# connecter.net
KiCad netlist of a schematic drawn in Altium Designer
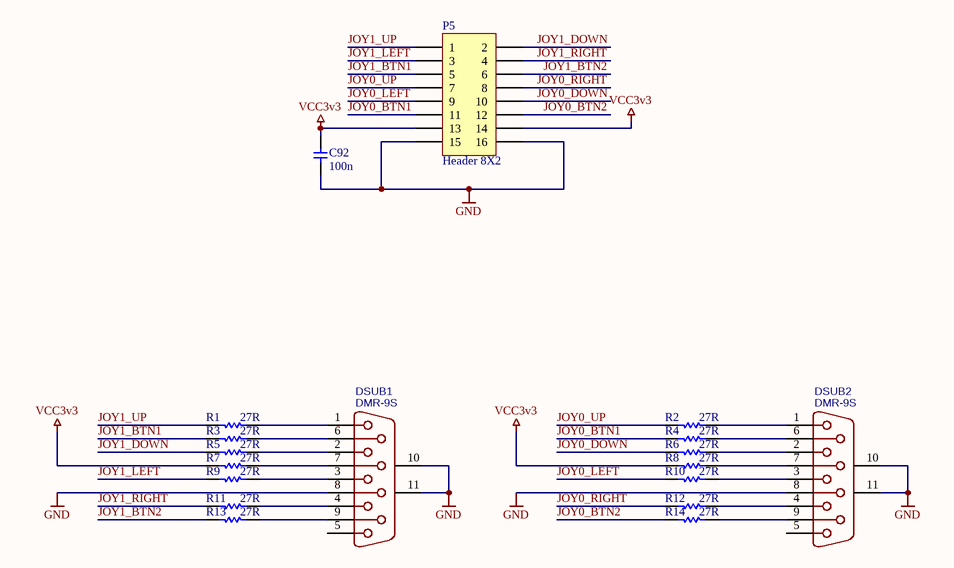
[diagram p0: connecter.SchDoc]

(export (version "E")
  (design (tool "Eeschema 10.0.6"))
  (components
    (comp (ref "C92")
      (value "100n")
      (footprint "0603")
      (description "0603 footprint non-polorised capacitor")
      (fields (field (name "Comment") "0603"))
      (libsource (lib "Integrated Comp_lib") (part "CAP_0603"))
    )
    (comp (ref "DSUB1")
      (value "DMR-9S")
      (footprint "DSUB-TH_DMR-9S")
      (fields (field (name "BOM_SUPPLIER PART") "C141882") (field (name "CONTRIBUTOR") "LCSC"))
      (libsource (lib "altium-import") (part "root_0_DMR-9S_"))
    )
    (comp (ref "DSUB2")
      (value "DMR-9S")
      (footprint "DSUB-TH_DMR-9S")
      (fields (field (name "BOM_SUPPLIER PART") "C141882") (field (name "CONTRIBUTOR") "LCSC"))
      (libsource (lib "altium-import") (part "root_0_DMR-9S_"))
    )
    (comp (ref "P5")
      (value "Header 8X2")
      (footprint "HDR2X8")
      (description "Header, 8-Pin, Dual row")
      (fields (field (name "PUBLISHER") "Altium Limited"))
      (libsource (lib "Miscellaneous Connectors") (part "Header 8X2"))
    )
    (comp (ref "R1")
      (value "27R")
      (footprint "0603")
      (description "0603 footprint resistor")
      (fields (field (name "Comment") "0603"))
      (libsource (lib "Integrated Comp_lib") (part "RES_0603"))
    )
    (comp (ref "R2")
      (value "27R")
      (footprint "0603")
      (description "0603 footprint resistor")
      (fields (field (name "Comment") "0603"))
      (libsource (lib "Integrated Comp_lib") (part "RES_0603"))
    )
    (comp (ref "R3")
      (value "27R")
      (footprint "0603")
      (description "0603 footprint resistor")
      (fields (field (name "Comment") "0603"))
      (libsource (lib "Integrated Comp_lib") (part "RES_0603"))
    )
    (comp (ref "R4")
      (value "27R")
      (footprint "0603")
      (description "0603 footprint resistor")
      (fields (field (name "Comment") "0603"))
      (libsource (lib "Integrated Comp_lib") (part "RES_0603"))
    )
    (comp (ref "R5")
      (value "27R")
      (footprint "0603")
      (description "0603 footprint resistor")
      (fields (field (name "Comment") "0603"))
      (libsource (lib "Integrated Comp_lib") (part "RES_0603"))
    )
    (comp (ref "R6")
      (value "27R")
      (footprint "0603")
      (description "0603 footprint resistor")
      (fields (field (name "Comment") "0603"))
      (libsource (lib "Integrated Comp_lib") (part "RES_0603"))
    )
    (comp (ref "R7")
      (value "27R")
      (footprint "0603")
      (description "0603 footprint resistor")
      (fields (field (name "Comment") "0603"))
      (libsource (lib "Integrated Comp_lib") (part "RES_0603"))
    )
    (comp (ref "R8")
      (value "27R")
      (footprint "0603")
      (description "0603 footprint resistor")
      (fields (field (name "Comment") "0603"))
      (libsource (lib "Integrated Comp_lib") (part "RES_0603"))
    )
    (comp (ref "R9")
      (value "27R")
      (footprint "0603")
      (description "0603 footprint resistor")
      (fields (field (name "Comment") "0603"))
      (libsource (lib "Integrated Comp_lib") (part "RES_0603"))
    )
    (comp (ref "R10")
      (value "27R")
      (footprint "0603")
      (description "0603 footprint resistor")
      (fields (field (name "Comment") "0603"))
      (libsource (lib "Integrated Comp_lib") (part "RES_0603"))
    )
    (comp (ref "R11")
      (value "27R")
      (footprint "0603")
      (description "0603 footprint resistor")
      (fields (field (name "Comment") "0603"))
      (libsource (lib "Integrated Comp_lib") (part "RES_0603"))
    )
    (comp (ref "R12")
      (value "27R")
      (footprint "0603")
      (description "0603 footprint resistor")
      (fields (field (name "Comment") "0603"))
      (libsource (lib "Integrated Comp_lib") (part "RES_0603"))
    )
    (comp (ref "R13")
      (value "27R")
      (footprint "0603")
      (description "0603 footprint resistor")
      (fields (field (name "Comment") "0603"))
      (libsource (lib "Integrated Comp_lib") (part "RES_0603"))
    )
    (comp (ref "R14")
      (value "27R")
      (footprint "0603")
      (description "0603 footprint resistor")
      (fields (field (name "Comment") "0603"))
      (libsource (lib "Integrated Comp_lib") (part "RES_0603"))
    )
  )
  (nets
    (net (code "1") (name "/JOY0_BTN1") (class "Default")
      (node (ref "P5") (pin "11") (pinfunction "11_11") (pintype "passive"))
      (node (ref "R4") (pin "2") (pinfunction "2_2") (pintype "passive"))
    )
    (net (code "2") (name "/JOY0_BTN2") (class "Default")
      (node (ref "P5") (pin "12") (pinfunction "12_12") (pintype "passive"))
      (node (ref "R14") (pin "2") (pinfunction "2_2") (pintype "passive"))
    )
    (net (code "3") (name "/JOY0_DOWN") (class "Default")
      (node (ref "P5") (pin "10") (pinfunction "10_10") (pintype "passive"))
      (node (ref "R6") (pin "2") (pinfunction "2_2") (pintype "passive"))
    )
    (net (code "4") (name "/JOY0_LEFT") (class "Default")
      (node (ref "P5") (pin "9") (pinfunction "9_9") (pintype "passive"))
      (node (ref "R10") (pin "2") (pinfunction "2_2") (pintype "passive"))
    )
    (net (code "5") (name "/JOY0_RIGHT") (class "Default")
      (node (ref "P5") (pin "8") (pinfunction "8_8") (pintype "passive"))
      (node (ref "R12") (pin "2") (pinfunction "2_2") (pintype "passive"))
    )
    (net (code "6") (name "/JOY0_UP") (class "Default")
      (node (ref "P5") (pin "7") (pinfunction "7_7") (pintype "passive"))
      (node (ref "R2") (pin "2") (pinfunction "2_2") (pintype "passive"))
    )
    (net (code "7") (name "/JOY1_BTN1") (class "Default")
      (node (ref "P5") (pin "5") (pinfunction "5_5") (pintype "passive"))
      (node (ref "R3") (pin "2") (pinfunction "2_2") (pintype "passive"))
    )
    (net (code "8") (name "/JOY1_BTN2") (class "Default")
      (node (ref "P5") (pin "6") (pinfunction "6_6") (pintype "passive"))
      (node (ref "R13") (pin "2") (pinfunction "2_2") (pintype "passive"))
    )
    (net (code "9") (name "/JOY1_DOWN") (class "Default")
      (node (ref "P5") (pin "2") (pinfunction "2_2") (pintype "passive"))
      (node (ref "R5") (pin "2") (pinfunction "2_2") (pintype "passive"))
    )
    (net (code "10") (name "/JOY1_LEFT") (class "Default")
      (node (ref "P5") (pin "3") (pinfunction "3_3") (pintype "passive"))
      (node (ref "R9") (pin "2") (pinfunction "2_2") (pintype "passive"))
    )
    (net (code "11") (name "/JOY1_RIGHT") (class "Default")
      (node (ref "P5") (pin "4") (pinfunction "4_4") (pintype "passive"))
      (node (ref "R11") (pin "2") (pinfunction "2_2") (pintype "passive"))
    )
    (net (code "12") (name "/JOY1_UP") (class "Default")
      (node (ref "P5") (pin "1") (pinfunction "1_1") (pintype "passive"))
      (node (ref "R1") (pin "2") (pinfunction "2_2") (pintype "passive"))
    )
    (net (code "13") (name "GND") (class "Default")
      (node (ref "C92") (pin "2") (pinfunction "2_2") (pintype "passive"))
      (node (ref "DSUB1") (pin "10") (pinfunction "MH1_10") (pintype "passive"))
      (node (ref "DSUB1") (pin "11") (pinfunction "MH2_11") (pintype "passive"))
      (node (ref "DSUB1") (pin "8") (pinfunction "8_8") (pintype "passive"))
      (node (ref "DSUB2") (pin "10") (pinfunction "MH1_10") (pintype "passive"))
      (node (ref "DSUB2") (pin "11") (pinfunction "MH2_11") (pintype "passive"))
      (node (ref "DSUB2") (pin "8") (pinfunction "8_8") (pintype "passive"))
      (node (ref "P5") (pin "15") (pinfunction "15_15") (pintype "passive"))
      (node (ref "P5") (pin "16") (pinfunction "16_16") (pintype "passive"))
    )
    (net (code "14") (name "Net-(DSUB1-Pad1)") (class "Default")
      (node (ref "DSUB1") (pin "1") (pinfunction "1_1") (pintype "passive"))
      (node (ref "R1") (pin "1") (pinfunction "1_1") (pintype "passive"))
    )
    (net (code "15") (name "Net-(DSUB1-Pad2)") (class "Default")
      (node (ref "DSUB1") (pin "2") (pinfunction "2_2") (pintype "passive"))
      (node (ref "R5") (pin "1") (pinfunction "1_1") (pintype "passive"))
    )
    (net (code "16") (name "Net-(DSUB1-Pad3)") (class "Default")
      (node (ref "DSUB1") (pin "3") (pinfunction "3_3") (pintype "passive"))
      (node (ref "R9") (pin "1") (pinfunction "1_1") (pintype "passive"))
    )
    (net (code "17") (name "Net-(DSUB1-Pad4)") (class "Default")
      (node (ref "DSUB1") (pin "4") (pinfunction "4_4") (pintype "passive"))
      (node (ref "R11") (pin "1") (pinfunction "1_1") (pintype "passive"))
    )
    (net (code "18") (name "Net-(DSUB1-Pad6)") (class "Default")
      (node (ref "DSUB1") (pin "6") (pinfunction "6_6") (pintype "passive"))
      (node (ref "R3") (pin "1") (pinfunction "1_1") (pintype "passive"))
    )
    (net (code "19") (name "Net-(DSUB1-Pad7)") (class "Default")
      (node (ref "DSUB1") (pin "7") (pinfunction "7_7") (pintype "passive"))
      (node (ref "R7") (pin "1") (pinfunction "1_1") (pintype "passive"))
    )
    (net (code "20") (name "Net-(DSUB1-Pad9)") (class "Default")
      (node (ref "DSUB1") (pin "9") (pinfunction "9_9") (pintype "passive"))
      (node (ref "R13") (pin "1") (pinfunction "1_1") (pintype "passive"))
    )
    (net (code "21") (name "Net-(DSUB2-Pad1)") (class "Default")
      (node (ref "DSUB2") (pin "1") (pinfunction "1_1") (pintype "passive"))
      (node (ref "R2") (pin "1") (pinfunction "1_1") (pintype "passive"))
    )
    (net (code "22") (name "Net-(DSUB2-Pad2)") (class "Default")
      (node (ref "DSUB2") (pin "2") (pinfunction "2_2") (pintype "passive"))
      (node (ref "R6") (pin "1") (pinfunction "1_1") (pintype "passive"))
    )
    (net (code "23") (name "Net-(DSUB2-Pad3)") (class "Default")
      (node (ref "DSUB2") (pin "3") (pinfunction "3_3") (pintype "passive"))
      (node (ref "R10") (pin "1") (pinfunction "1_1") (pintype "passive"))
    )
    (net (code "24") (name "Net-(DSUB2-Pad4)") (class "Default")
      (node (ref "DSUB2") (pin "4") (pinfunction "4_4") (pintype "passive"))
      (node (ref "R12") (pin "1") (pinfunction "1_1") (pintype "passive"))
    )
    (net (code "25") (name "Net-(DSUB2-Pad6)") (class "Default")
      (node (ref "DSUB2") (pin "6") (pinfunction "6_6") (pintype "passive"))
      (node (ref "R4") (pin "1") (pinfunction "1_1") (pintype "passive"))
    )
    (net (code "26") (name "Net-(DSUB2-Pad7)") (class "Default")
      (node (ref "DSUB2") (pin "7") (pinfunction "7_7") (pintype "passive"))
      (node (ref "R8") (pin "1") (pinfunction "1_1") (pintype "passive"))
    )
    (net (code "27") (name "Net-(DSUB2-Pad9)") (class "Default")
      (node (ref "DSUB2") (pin "9") (pinfunction "9_9") (pintype "passive"))
      (node (ref "R14") (pin "1") (pinfunction "1_1") (pintype "passive"))
    )
    (net (code "28") (name "VCC3v3") (class "Default")
      (node (ref "C92") (pin "1") (pinfunction "1_1") (pintype "passive"))
      (node (ref "P5") (pin "13") (pinfunction "13_13") (pintype "passive"))
      (node (ref "P5") (pin "14") (pinfunction "14_14") (pintype "passive"))
      (node (ref "R7") (pin "2") (pinfunction "2_2") (pintype "passive"))
      (node (ref "R8") (pin "2") (pinfunction "2_2") (pintype "passive"))
    )
    (net (code "29") (name "unconnected-(DSUB1-Pad5)") (class "Default")
      (node (ref "DSUB1") (pin "5") (pinfunction "5_5") (pintype "passive"))
    )
    (net (code "30") (name "unconnected-(DSUB2-Pad5)") (class "Default")
      (node (ref "DSUB2") (pin "5") (pinfunction "5_5") (pintype "passive"))
    )
  )
)
